# 555srvc.net
KiCad netlist of a schematic drawn in EAGLE
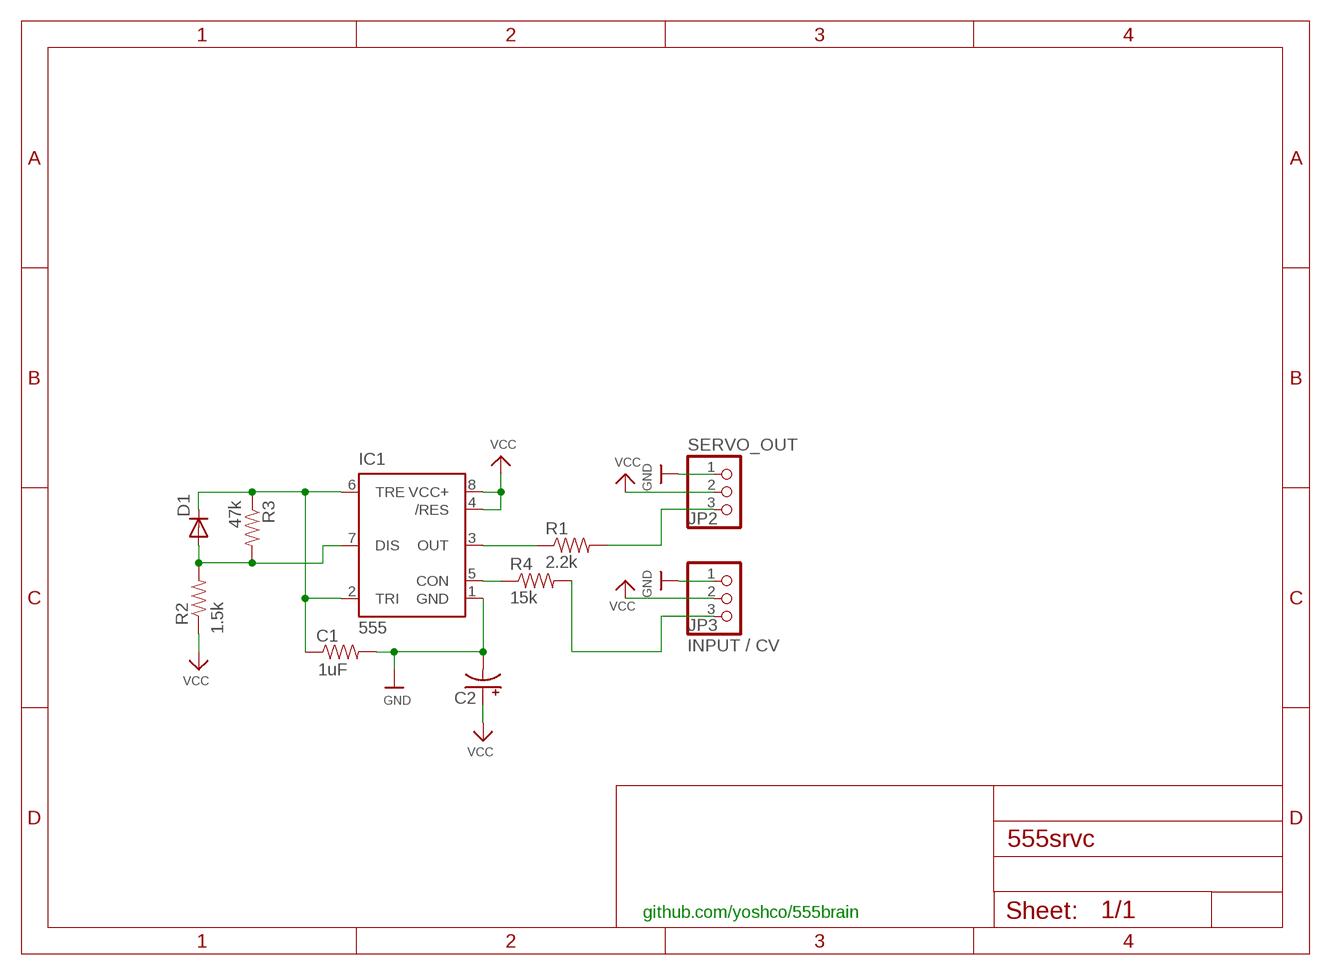
[diagram p0: schematic, sheet 1]

(export (version "E")
  (design (tool "Eeschema 10.0.6"))
  (components
    (comp (ref "C1")
      (value "1uF")
      (footprint "eagle-import:0805")
      (libsource (lib "eagle-import") (part "RESISTOR0805-RES"))
    )
    (comp (ref "C2")
      (value "CPOL-USE5-6")
      (footprint "eagle-import:E5-6")
      (libsource (lib "eagle-import") (part "CPOL-USE5-6"))
    )
    (comp (ref "D1")
      (value "DIODESOD-123")
      (footprint "eagle-import:SOD-123")
      (libsource (lib "eagle-import") (part "DIODESOD-123"))
    )
    (comp (ref "IC1")
      (value "555")
      (footprint "eagle-import:SO08")
      (libsource (lib "eagle-import") (part "NE555D"))
    )
    (comp (ref "JP2")
      (value "SERVO_OUT")
      (footprint "eagle-import:1X03-CLEANBIG")
      (libsource (lib "eagle-import") (part "PINHD-1X3CB"))
    )
    (comp (ref "JP3")
      (value "INPUT / CV")
      (footprint "eagle-import:1X03-CLEANBIG")
      (libsource (lib "eagle-import") (part "PINHD-1X3CB"))
    )
    (comp (ref "R1")
      (value "2.2k")
      (footprint "eagle-import:0805")
      (libsource (lib "eagle-import") (part "RESISTOR0805-RES"))
    )
    (comp (ref "R2")
      (value "1.5k")
      (footprint "eagle-import:0805")
      (libsource (lib "eagle-import") (part "RESISTOR0805-RES"))
    )
    (comp (ref "R3")
      (value "47k")
      (footprint "eagle-import:0805")
      (libsource (lib "eagle-import") (part "RESISTOR0805-RES"))
    )
    (comp (ref "R4")
      (value "15k")
      (footprint "eagle-import:0805")
      (libsource (lib "eagle-import") (part "RESISTOR0805-RES"))
    )
  )
  (nets
    (net (code "1") (name "GND") (class "Default")
      (node (ref "C1") (pin "2") (pinfunction "2_2") (pintype "passive"))
      (node (ref "C2") (pin "-") (pinfunction "-_-") (pintype "passive"))
      (node (ref "IC1") (pin "1") (pinfunction "GND_1") (pintype "power_in"))
      (node (ref "JP2") (pin "1") (pinfunction "1_1") (pintype "passive"))
      (node (ref "JP3") (pin "1") (pinfunction "1_1") (pintype "passive"))
    )
    (net (code "2") (name "Net-(IC1-CON)") (class "Default")
      (node (ref "IC1") (pin "5") (pinfunction "CON_5") (pintype "input"))
      (node (ref "R4") (pin "1") (pinfunction "1_1") (pintype "passive"))
    )
    (net (code "3") (name "Net-(IC1-DIS)") (class "Default")
      (node (ref "D1") (pin "A") (pinfunction "A_A") (pintype "passive"))
      (node (ref "IC1") (pin "7") (pinfunction "DIS_7") (pintype "input"))
      (node (ref "R2") (pin "2") (pinfunction "2_2") (pintype "passive"))
      (node (ref "R3") (pin "2") (pinfunction "2_2") (pintype "passive"))
    )
    (net (code "4") (name "Net-(IC1-OUT)") (class "Default")
      (node (ref "IC1") (pin "3") (pinfunction "OUT_3") (pintype "output"))
      (node (ref "R1") (pin "1") (pinfunction "1_1") (pintype "passive"))
    )
    (net (code "5") (name "Net-(IC1-TRE)") (class "Default")
      (node (ref "C1") (pin "1") (pinfunction "1_1") (pintype "passive"))
      (node (ref "D1") (pin "C") (pinfunction "C_C") (pintype "passive"))
      (node (ref "IC1") (pin "2") (pinfunction "TRI_2") (pintype "input"))
      (node (ref "IC1") (pin "6") (pinfunction "TRE_6") (pintype "input"))
      (node (ref "R3") (pin "1") (pinfunction "1_1") (pintype "passive"))
    )
    (net (code "6") (name "Net-(JP2-Pad3)") (class "Default")
      (node (ref "JP2") (pin "3") (pinfunction "3_3") (pintype "passive"))
      (node (ref "R1") (pin "2") (pinfunction "2_2") (pintype "passive"))
    )
    (net (code "7") (name "Net-(JP3-Pad3)") (class "Default")
      (node (ref "JP3") (pin "3") (pinfunction "3_3") (pintype "passive"))
      (node (ref "R4") (pin "2") (pinfunction "2_2") (pintype "passive"))
    )
    (net (code "8") (name "VCC") (class "Default")
      (node (ref "C2") (pin "+") (pinfunction "+_+") (pintype "passive"))
      (node (ref "IC1") (pin "4") (pinfunction "/RES_4") (pintype "input"))
      (node (ref "IC1") (pin "8") (pinfunction "VCC+_8") (pintype "power_in"))
      (node (ref "JP2") (pin "2") (pinfunction "2_2") (pintype "passive"))
      (node (ref "JP3") (pin "2") (pinfunction "2_2") (pintype "passive"))
      (node (ref "R2") (pin "1") (pinfunction "1_1") (pintype "passive"))
    )
  )
)
